# usbtinyisp_th.net
KiCad netlist of a schematic drawn in EAGLE
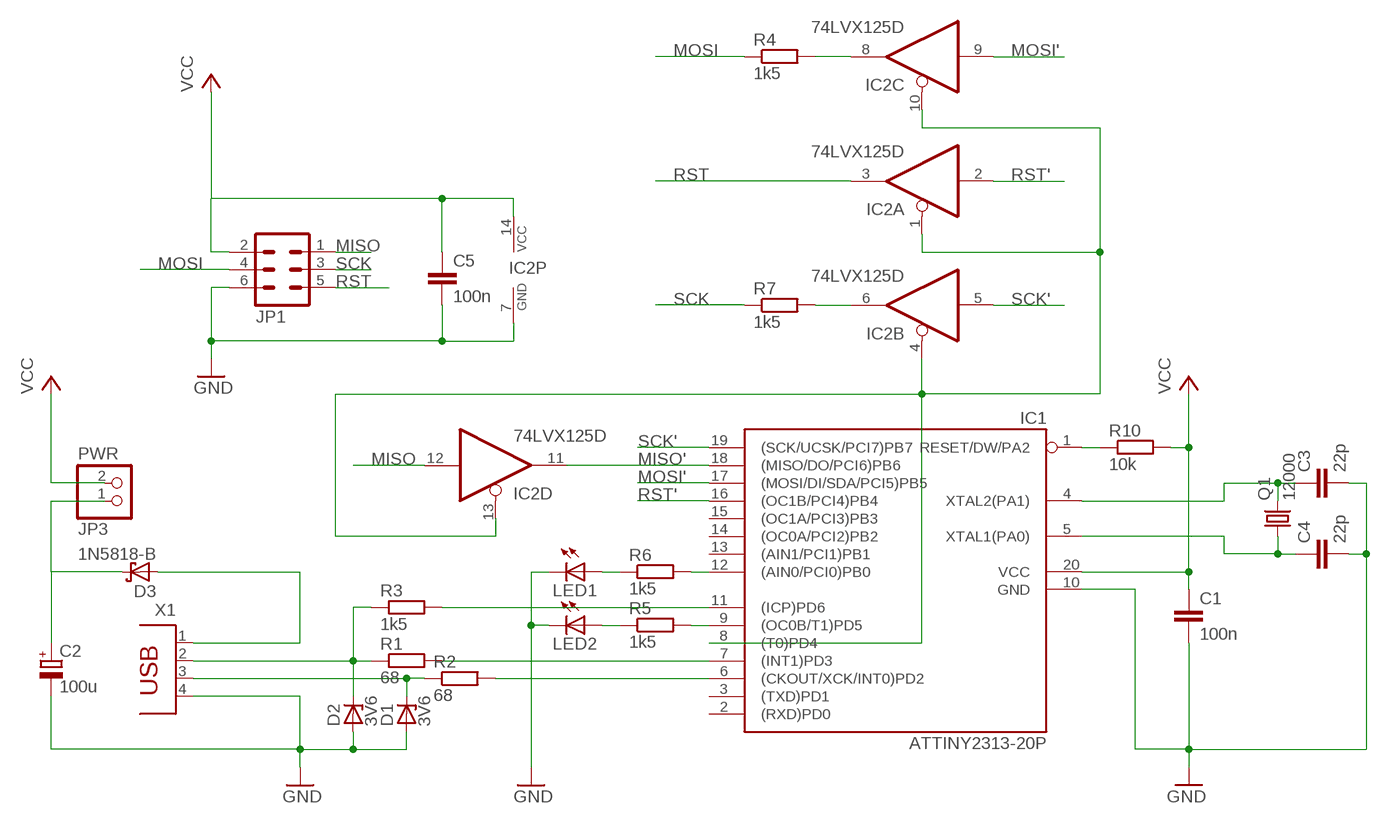
[diagram p0: schematic, sheet 1]

(export (version "E")
  (design (tool "Eeschema 10.0.6"))
  (components
    (comp (ref "C1")
      (value "100n")
      (footprint "eagle-import:C025-025X050")
      (libsource (lib "eagle-import") (part "C-EU025-025X050"))
    )
    (comp (ref "C2")
      (value "100u")
      (footprint "eagle-import:E2,5-6")
      (libsource (lib "eagle-import") (part "CPOL-EUE2.5-6"))
    )
    (comp (ref "C3")
      (value "22p")
      (footprint "eagle-import:C025-025X050")
      (libsource (lib "eagle-import") (part "C-EU025-025X050"))
    )
    (comp (ref "C4")
      (value "22p")
      (footprint "eagle-import:C025-025X050")
      (libsource (lib "eagle-import") (part "C-EU025-025X050"))
    )
    (comp (ref "C5")
      (value "100n")
      (footprint "eagle-import:C025-025X050")
      (libsource (lib "eagle-import") (part "C-EU025-025X050"))
    )
    (comp (ref "D1")
      (value "3V6")
      (footprint "eagle-import:DO35Z10")
      (libsource (lib "eagle-import") (part "ZENER-DIODEDO35Z10"))
    )
    (comp (ref "D2")
      (value "3V6")
      (footprint "eagle-import:DO35Z10")
      (libsource (lib "eagle-import") (part "ZENER-DIODEDO35Z10"))
    )
    (comp (ref "D3")
      (value "1N5818-B")
      (footprint "eagle-import:DO41-7.6")
      (libsource (lib "eagle-import") (part "1N5817-B"))
    )
    (comp (ref "IC1")
      (value "ATTINY2313-20P")
      (footprint "eagle-import:DIL20")
      (libsource (lib "eagle-import") (part "ATTINY2313P-20"))
    )
    (comp (ref "IC2")
      (value "74LVX125D")
      (footprint "eagle-import:DIL14")
      (libsource (lib "eagle-import") (part "74125NHC"))
    )
    (comp (ref "JP1")
      (value "MA03-2")
      (footprint "eagle-import:MA03-2")
      (libsource (lib "eagle-import") (part "MA03-2"))
    )
    (comp (ref "JP3")
      (value "PWR")
      (footprint "eagle-import:1X02")
      (libsource (lib "eagle-import") (part "PINHD-1X2"))
    )
    (comp (ref "LED1")
      (value "LED5MM")
      (footprint "eagle-import:LED5MM")
      (libsource (lib "eagle-import") (part "LED5MM"))
    )
    (comp (ref "LED2")
      (value "LED5MM")
      (footprint "eagle-import:LED5MM")
      (libsource (lib "eagle-import") (part "LED5MM"))
    )
    (comp (ref "Q1")
      (value "12000")
      (footprint "eagle-import:HC49U-V")
      (libsource (lib "eagle-import") (part "CRYSTALHC49U-V"))
    )
    (comp (ref "R1")
      (value "68")
      (footprint "eagle-import:0204_7")
      (libsource (lib "eagle-import") (part "R-EU_0204/7"))
    )
    (comp (ref "R2")
      (value "68")
      (footprint "eagle-import:0204_7")
      (libsource (lib "eagle-import") (part "R-EU_0204/7"))
    )
    (comp (ref "R3")
      (value "1k5")
      (footprint "eagle-import:0204_7")
      (libsource (lib "eagle-import") (part "R-EU_0204/7"))
    )
    (comp (ref "R4")
      (value "1k5")
      (footprint "eagle-import:0204_7")
      (libsource (lib "eagle-import") (part "R-EU_0204/7"))
    )
    (comp (ref "R5")
      (value "1k5")
      (footprint "eagle-import:0204_7")
      (libsource (lib "eagle-import") (part "R-EU_0204/7"))
    )
    (comp (ref "R6")
      (value "1k5")
      (footprint "eagle-import:0204_7")
      (libsource (lib "eagle-import") (part "R-EU_0204/7"))
    )
    (comp (ref "R7")
      (value "1k5")
      (footprint "eagle-import:0204_7")
      (libsource (lib "eagle-import") (part "R-EU_0204/7"))
    )
    (comp (ref "R10")
      (value "10k")
      (footprint "eagle-import:0204_7")
      (libsource (lib "eagle-import") (part "R-EU_0204/7"))
    )
    (comp (ref "X1")
      (value "PN61729")
      (footprint "eagle-import:PN61729")
      (libsource (lib "eagle-import") (part "PN61729"))
    )
  )
  (nets
    (net (code "1") (name "/MISO") (class "Default")
      (node (ref "IC2") (pin "12") (pinfunction "I_12") (pintype "input"))
      (node (ref "JP1") (pin "1") (pinfunction "1_1") (pintype "passive"))
    )
    (net (code "2") (name "/MISO'") (class "Default")
      (node (ref "IC1") (pin "18") (pinfunction "(MISO/DO/PCI6)PB6_18") (pintype "bidirectional"))
      (node (ref "IC2") (pin "11") (pinfunction "O_11") (pintype "tri_state"))
    )
    (net (code "3") (name "/MOSI") (class "Default")
      (node (ref "JP1") (pin "4") (pinfunction "4_4") (pintype "passive"))
      (node (ref "R4") (pin "1") (pinfunction "1_1") (pintype "passive"))
    )
    (net (code "4") (name "/MOSI'") (class "Default")
      (node (ref "IC1") (pin "17") (pinfunction "(MOSI/DI/SDA/PCI5)PB5_17") (pintype "bidirectional"))
      (node (ref "IC2") (pin "9") (pinfunction "I_9") (pintype "input"))
    )
    (net (code "5") (name "/RST") (class "Default")
      (node (ref "IC2") (pin "3") (pinfunction "O_3") (pintype "tri_state"))
      (node (ref "JP1") (pin "5") (pinfunction "5_5") (pintype "passive"))
    )
    (net (code "6") (name "/RST'") (class "Default")
      (node (ref "IC1") (pin "16") (pinfunction "(OC1B/PCI4)PB4_16") (pintype "bidirectional"))
      (node (ref "IC2") (pin "2") (pinfunction "I_2") (pintype "input"))
    )
    (net (code "7") (name "/SCK") (class "Default")
      (node (ref "JP1") (pin "3") (pinfunction "3_3") (pintype "passive"))
      (node (ref "R7") (pin "1") (pinfunction "1_1") (pintype "passive"))
    )
    (net (code "8") (name "/SCK'") (class "Default")
      (node (ref "IC1") (pin "19") (pinfunction "(SCK/UCSK/PCI7)PB7_19") (pintype "bidirectional"))
      (node (ref "IC2") (pin "5") (pinfunction "I_5") (pintype "input"))
    )
    (net (code "9") (name "GND") (class "Default")
      (node (ref "C1") (pin "2") (pinfunction "2_2") (pintype "passive"))
      (node (ref "C2") (pin "-") (pinfunction "-_-") (pintype "passive"))
      (node (ref "C3") (pin "2") (pinfunction "2_2") (pintype "passive"))
      (node (ref "C4") (pin "2") (pinfunction "2_2") (pintype "passive"))
      (node (ref "C5") (pin "2") (pinfunction "2_2") (pintype "passive"))
      (node (ref "D1") (pin "A") (pinfunction "A_A") (pintype "passive"))
      (node (ref "D2") (pin "A") (pinfunction "A_A") (pintype "passive"))
      (node (ref "IC1") (pin "10") (pinfunction "GND_10") (pintype "power_in"))
      (node (ref "IC2") (pin "7") (pinfunction "GND_7") (pintype "power_in"))
      (node (ref "JP1") (pin "6") (pinfunction "6_6") (pintype "passive"))
      (node (ref "LED1") (pin "K") (pinfunction "C_K") (pintype "passive"))
      (node (ref "LED2") (pin "K") (pinfunction "C_K") (pintype "passive"))
      (node (ref "X1") (pin "4") (pinfunction "4_4") (pintype "bidirectional"))
    )
    (net (code "10") (name "Net-(C2-Pad+)") (class "Default")
      (node (ref "C2") (pin "+") (pinfunction "+_+") (pintype "passive"))
      (node (ref "D3") (pin "C") (pinfunction "C_C") (pintype "passive"))
      (node (ref "JP3") (pin "1") (pinfunction "1_1") (pintype "passive"))
    )
    (net (code "11") (name "Net-(D1-PadC)") (class "Default")
      (node (ref "D1") (pin "C") (pinfunction "C_C") (pintype "passive"))
      (node (ref "R2") (pin "1") (pinfunction "1_1") (pintype "passive"))
      (node (ref "X1") (pin "3") (pinfunction "3_3") (pintype "bidirectional"))
    )
    (net (code "12") (name "Net-(D2-PadC)") (class "Default")
      (node (ref "D2") (pin "C") (pinfunction "C_C") (pintype "passive"))
      (node (ref "R1") (pin "1") (pinfunction "1_1") (pintype "passive"))
      (node (ref "R3") (pin "1") (pinfunction "1_1") (pintype "passive"))
      (node (ref "X1") (pin "2") (pinfunction "2_2") (pintype "bidirectional"))
    )
    (net (code "13") (name "Net-(D3-PadA)") (class "Default")
      (node (ref "D3") (pin "A") (pinfunction "A_A") (pintype "passive"))
      (node (ref "X1") (pin "1") (pinfunction "1_1") (pintype "bidirectional"))
    )
    (net (code "14") (name "Net-(IC1-(AIN0{slash}PCI0)PB0)") (class "Default")
      (node (ref "IC1") (pin "12") (pinfunction "(AIN0/PCI0)PB0_12") (pintype "bidirectional"))
      (node (ref "R6") (pin "2") (pinfunction "2_2") (pintype "passive"))
    )
    (net (code "15") (name "Net-(IC1-(CKOUT{slash}XCK{slash}INT0)PD2)") (class "Default")
      (node (ref "IC1") (pin "6") (pinfunction "(CKOUT/XCK/INT0)PD2_6") (pintype "bidirectional"))
      (node (ref "R2") (pin "2") (pinfunction "2_2") (pintype "passive"))
    )
    (net (code "16") (name "Net-(IC1-(ICP)PD6)") (class "Default")
      (node (ref "IC1") (pin "11") (pinfunction "(ICP)PD6_11") (pintype "bidirectional"))
      (node (ref "R3") (pin "2") (pinfunction "2_2") (pintype "passive"))
    )
    (net (code "17") (name "Net-(IC1-(INT1)PD3)") (class "Default")
      (node (ref "IC1") (pin "7") (pinfunction "(INT1)PD3_7") (pintype "bidirectional"))
      (node (ref "R1") (pin "2") (pinfunction "2_2") (pintype "passive"))
    )
    (net (code "18") (name "Net-(IC1-(OC0B{slash}T1)PD5)") (class "Default")
      (node (ref "IC1") (pin "9") (pinfunction "(OC0B/T1)PD5_9") (pintype "bidirectional"))
      (node (ref "R5") (pin "2") (pinfunction "2_2") (pintype "passive"))
    )
    (net (code "19") (name "Net-(IC1-(T0)PD4)") (class "Default")
      (node (ref "IC1") (pin "8") (pinfunction "(T0)PD4_8") (pintype "bidirectional"))
      (node (ref "IC2") (pin "1") (pinfunction "OE_1") (pintype "input"))
      (node (ref "IC2") (pin "10") (pinfunction "OE_10") (pintype "input"))
      (node (ref "IC2") (pin "13") (pinfunction "OE_13") (pintype "input"))
      (node (ref "IC2") (pin "4") (pinfunction "OE_4") (pintype "input"))
    )
    (net (code "20") (name "Net-(IC1-RESET{slash}DW{slash}PA2)") (class "Default")
      (node (ref "IC1") (pin "1") (pinfunction "RESET/DW/PA2_1") (pintype "bidirectional"))
      (node (ref "R10") (pin "1") (pinfunction "1_1") (pintype "passive"))
    )
    (net (code "21") (name "Net-(IC1-XTAL1(PA0))") (class "Default")
      (node (ref "C4") (pin "1") (pinfunction "1_1") (pintype "passive"))
      (node (ref "IC1") (pin "5") (pinfunction "XTAL1(PA0)_5") (pintype "bidirectional"))
      (node (ref "Q1") (pin "1") (pinfunction "1_1") (pintype "passive"))
    )
    (net (code "22") (name "Net-(IC1-XTAL2(PA1))") (class "Default")
      (node (ref "C3") (pin "1") (pinfunction "1_1") (pintype "passive"))
      (node (ref "IC1") (pin "4") (pinfunction "XTAL2(PA1)_4") (pintype "bidirectional"))
      (node (ref "Q1") (pin "2") (pinfunction "2_2") (pintype "passive"))
    )
    (net (code "23") (name "Net-(IC2B-O)") (class "Default")
      (node (ref "IC2") (pin "6") (pinfunction "O_6") (pintype "tri_state"))
      (node (ref "R7") (pin "2") (pinfunction "2_2") (pintype "passive"))
    )
    (net (code "24") (name "Net-(IC2C-O)") (class "Default")
      (node (ref "IC2") (pin "8") (pinfunction "O_8") (pintype "tri_state"))
      (node (ref "R4") (pin "2") (pinfunction "2_2") (pintype "passive"))
    )
    (net (code "25") (name "Net-(LED1-PadA)") (class "Default")
      (node (ref "LED1") (pin "A") (pinfunction "A_A") (pintype "passive"))
      (node (ref "R6") (pin "1") (pinfunction "1_1") (pintype "passive"))
    )
    (net (code "26") (name "Net-(LED2-PadA)") (class "Default")
      (node (ref "LED2") (pin "A") (pinfunction "A_A") (pintype "passive"))
      (node (ref "R5") (pin "1") (pinfunction "1_1") (pintype "passive"))
    )
    (net (code "27") (name "VCC") (class "Default")
      (node (ref "C1") (pin "1") (pinfunction "1_1") (pintype "passive"))
      (node (ref "C5") (pin "1") (pinfunction "1_1") (pintype "passive"))
      (node (ref "IC1") (pin "20") (pinfunction "VCC_20") (pintype "power_in"))
      (node (ref "IC2") (pin "14") (pinfunction "VCC_14") (pintype "power_in"))
      (node (ref "JP1") (pin "2") (pinfunction "2_2") (pintype "passive"))
      (node (ref "JP3") (pin "2") (pinfunction "2_2") (pintype "passive"))
      (node (ref "R10") (pin "2") (pinfunction "2_2") (pintype "passive"))
    )
    (net (code "28") (name "unconnected-(IC1-(AIN1{slash}PCI1)PB1-Pad13)") (class "Default")
      (node (ref "IC1") (pin "13") (pinfunction "(AIN1/PCI1)PB1_13") (pintype "bidirectional"))
    )
    (net (code "29") (name "unconnected-(IC1-(OC0A{slash}PCI2)PB2-Pad14)") (class "Default")
      (node (ref "IC1") (pin "14") (pinfunction "(OC0A/PCI2)PB2_14") (pintype "bidirectional"))
    )
    (net (code "30") (name "unconnected-(IC1-(OC1A{slash}PCI3)PB3-Pad15)") (class "Default")
      (node (ref "IC1") (pin "15") (pinfunction "(OC1A/PCI3)PB3_15") (pintype "bidirectional"))
    )
    (net (code "31") (name "unconnected-(IC1-(RXD)PD0-Pad2)") (class "Default")
      (node (ref "IC1") (pin "2") (pinfunction "(RXD)PD0_2") (pintype "bidirectional"))
    )
    (net (code "32") (name "unconnected-(IC1-(TXD)PD1-Pad3)") (class "Default")
      (node (ref "IC1") (pin "3") (pinfunction "(TXD)PD1_3") (pintype "bidirectional"))
    )
  )
)
